# UTM53.net
KiCad netlist of a schematic drawn in Altium Designer
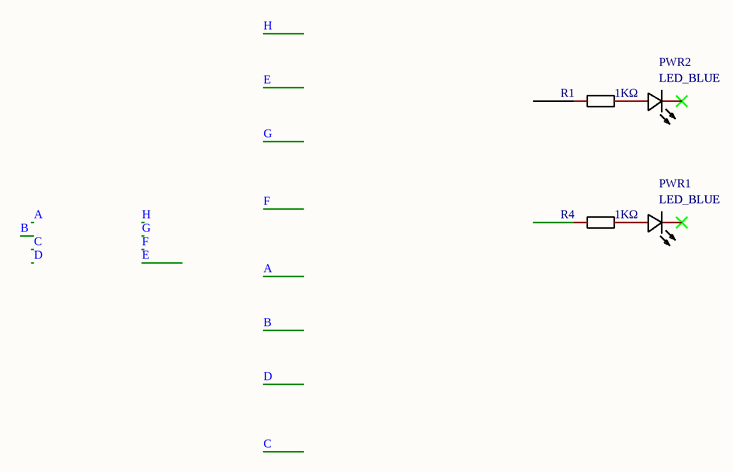
[diagram p0: UTM53.schdoc]

(export (version "E")
  (design (tool "Eeschema 10.0.6"))
  (components
    (comp (ref "PWR1")
      (value "LED_BLUE")
      (description "Emitted Color:blue")
      (fields
        (field (name "NAME") "LED_BLUE")
        (field (name "MANUFACTURER") "国星光电")
        (field (name "MANUFACTURER PART") "NCD0805B2")
      )
      (libsource (lib "altium-import") (part "root_2_NCD0805B2_"))
    )
    (comp (ref "PWR2")
      (value "LED_BLUE")
      (description "Emitted Color:blue")
      (fields
        (field (name "NAME") "LED_BLUE")
        (field (name "MANUFACTURER") "国星光电")
        (field (name "MANUFACTURER PART") "NCD0805B2")
      )
      (libsource (lib "altium-import") (part "root_2_NCD0805B2_"))
    )
    (comp (ref "R1")
      (value "0603WAF1001T5E")
      (fields (field (name "LCSC PART NAME") "1KΩ") (field (name "MANUFACTURER") "UNI-ROYAL(厚声)"))
      (libsource (lib "altium-import") (part "root_0_0603WAF1001T5E_"))
    )
    (comp (ref "R4")
      (value "0603WAF1001T5E")
      (fields (field (name "LCSC PART NAME") "1KΩ") (field (name "MANUFACTURER") "UNI-ROYAL(厚声)"))
      (libsource (lib "altium-import") (part "root_0_0603WAF1001T5E_"))
    )
  )
  (nets
    (net (code "9") (name "Net-(PWR1-+)") (class "Default")
      (node (ref "PWR1") (pin "2") (pinfunction "+_2") (pintype "passive"))
      (node (ref "R4") (pin "2") (pinfunction "2_2") (pintype "passive"))
    )
    (net (code "10") (name "Net-(PWR2-+)") (class "Default")
      (node (ref "PWR2") (pin "2") (pinfunction "+_2") (pintype "passive"))
      (node (ref "R1") (pin "2") (pinfunction "2_2") (pintype "passive"))
    )
    (net (code "11") (name "unconnected-(PWR1---Pad1)") (class "Default")
      (node (ref "PWR1") (pin "1") (pinfunction "-_1") (pintype "passive+no_connect"))
    )
    (net (code "12") (name "unconnected-(PWR2---Pad1)") (class "Default")
      (node (ref "PWR2") (pin "1") (pinfunction "-_1") (pintype "passive+no_connect"))
    )
    (net (code "13") (name "unconnected-(R1-Pad1)") (class "Default")
      (node (ref "R1") (pin "1") (pinfunction "1_1") (pintype "passive"))
    )
    (net (code "14") (name "unconnected-(R4-Pad1)") (class "Default")
      (node (ref "R4") (pin "1") (pinfunction "1_1") (pintype "passive"))
    )
  )
)
